# LV_Schematic.net
KiCad netlist of a schematic drawn in Altium Designer
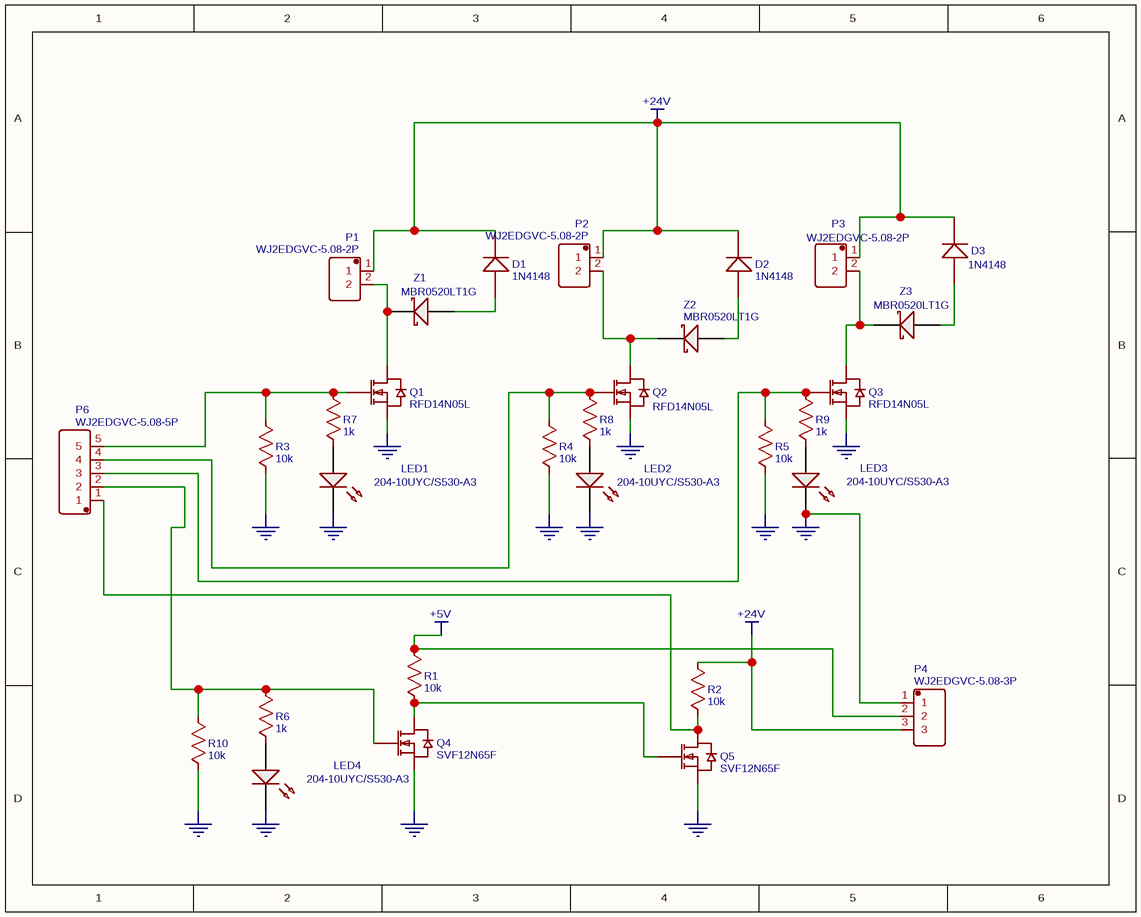
[diagram p0: LV+Schematic.schdoc]

(export (version "E")
  (design (tool "Eeschema 10.0.6"))
  (components
    (comp (ref "D1") (value "1N4148") (libsource (lib "") (part "root_1___1")))
    (comp (ref "D2") (value "1N4148") (libsource (lib "") (part "root_1___1")))
    (comp (ref "D3") (value "1N4148") (libsource (lib "") (part "root_1___1")))
    (comp (ref "LED1") (value "204-10UYC/S530-A3") (libsource (lib "altium-import") (part "root_3__")))
    (comp (ref "LED2") (value "204-10UYC/S530-A3") (libsource (lib "altium-import") (part "root_3__")))
    (comp (ref "LED3") (value "204-10UYC/S530-A3") (libsource (lib "altium-import") (part "root_3__")))
    (comp (ref "LED4") (value "204-10UYC/S530-A3") (libsource (lib "altium-import") (part "root_3__")))
    (comp (ref "P1")
      (value "WJ2EDGVC-5.08-2P")
      (fields (field (name "BOM_MANUFACTURER PART") "?"))
      (libsource (lib "") (part "root_0___3"))
    )
    (comp (ref "P2")
      (value "WJ2EDGVC-5.08-2P")
      (fields (field (name "BOM_MANUFACTURER PART") "?"))
      (libsource (lib "") (part "root_0___3"))
    )
    (comp (ref "P3")
      (value "WJ2EDGVC-5.08-2P")
      (fields (field (name "BOM_MANUFACTURER PART") "?"))
      (libsource (lib "") (part "root_0___3"))
    )
    (comp (ref "P4")
      (value "WJ2EDGVC-5.08-3P")
      (fields (field (name "BOM_MANUFACTURER PART") "?"))
      (libsource (lib "") (part "root_0___2"))
    )
    (comp (ref "P6")
      (value "WJ2EDGVC-5.08-5P")
      (fields (field (name "BOM_MANUFACTURER PART") "?"))
      (libsource (lib "altium-import") (part "root_2__"))
    )
    (comp (ref "Q1")
      (value "RFD14N05L")
      (fields (field (name "BOM_MANUFACTURER PART") "SVF12N65F"))
      (libsource (lib "altium-import") (part "root_0__"))
    )
    (comp (ref "Q2")
      (value "RFD14N05L")
      (fields (field (name "BOM_MANUFACTURER PART") "SVF12N65F"))
      (libsource (lib "altium-import") (part "root_0__"))
    )
    (comp (ref "Q3")
      (value "RFD14N05L")
      (fields (field (name "BOM_MANUFACTURER PART") "SVF12N65F"))
      (libsource (lib "altium-import") (part "root_0__"))
    )
    (comp (ref "Q4") (value "SVF12N65F") (libsource (lib "altium-import") (part "root_0__")))
    (comp (ref "Q5") (value "SVF12N65F") (libsource (lib "altium-import") (part "root_0__")))
    (comp (ref "R1")
      (value "10k")
      (fields (field (name "BOM_MANUFACTURER PART") "?"))
      (libsource (lib "altium-import") (part "root_1__"))
    )
    (comp (ref "R2")
      (value "10k")
      (fields (field (name "BOM_MANUFACTURER PART") "?"))
      (libsource (lib "altium-import") (part "root_1__"))
    )
    (comp (ref "R3")
      (value "10k")
      (fields (field (name "BOM_MANUFACTURER PART") "?"))
      (libsource (lib "altium-import") (part "root_1__"))
    )
    (comp (ref "R4")
      (value "10k")
      (fields (field (name "BOM_MANUFACTURER PART") "?"))
      (libsource (lib "altium-import") (part "root_1__"))
    )
    (comp (ref "R5")
      (value "10k")
      (fields (field (name "BOM_MANUFACTURER PART") "?"))
      (libsource (lib "altium-import") (part "root_1__"))
    )
    (comp (ref "R6")
      (value "1k")
      (fields (field (name "BOM_MANUFACTURER PART") "?"))
      (libsource (lib "altium-import") (part "root_1__"))
    )
    (comp (ref "R7")
      (value "1k")
      (fields (field (name "BOM_MANUFACTURER PART") "?"))
      (libsource (lib "altium-import") (part "root_1__"))
    )
    (comp (ref "R8")
      (value "1k")
      (fields (field (name "BOM_MANUFACTURER PART") "?"))
      (libsource (lib "altium-import") (part "root_1__"))
    )
    (comp (ref "R9")
      (value "1k")
      (fields (field (name "BOM_MANUFACTURER PART") "?"))
      (libsource (lib "altium-import") (part "root_1__"))
    )
    (comp (ref "R10")
      (value "10k")
      (fields (field (name "BOM_MANUFACTURER PART") "?"))
      (libsource (lib "altium-import") (part "root_1__"))
    )
    (comp (ref "Z1") (value "MBR0520LT1G") (libsource (lib "") (part "root_0___1")))
    (comp (ref "Z2") (value "MBR0520LT1G") (libsource (lib "") (part "root_0___1")))
    (comp (ref "Z3") (value "MBR0520LT1G") (libsource (lib "") (part "root_0___1")))
  )
  (nets
    (net (code "1") (name "+5V") (class "Default")
      (node (ref "P4") (pin "2") (pinfunction "2_2") (pintype "passive"))
      (node (ref "R1") (pin "2") (pinfunction "2_2") (pintype "passive"))
    )
    (net (code "2") (name "+24V") (class "Default")
      (node (ref "D1") (pin "2") (pinfunction "K_2") (pintype "passive"))
      (node (ref "D2") (pin "2") (pinfunction "K_2") (pintype "passive"))
      (node (ref "D3") (pin "2") (pinfunction "K_2") (pintype "passive"))
      (node (ref "P1") (pin "1") (pinfunction "1_1") (pintype "passive"))
      (node (ref "P2") (pin "1") (pinfunction "1_1") (pintype "passive"))
      (node (ref "P3") (pin "1") (pinfunction "1_1") (pintype "passive"))
      (node (ref "P4") (pin "3") (pinfunction "3_3") (pintype "passive"))
      (node (ref "R2") (pin "2") (pinfunction "2_2") (pintype "passive"))
    )
    (net (code "3") (name "GND") (class "Default")
      (node (ref "LED1") (pin "2") (pinfunction "C_2") (pintype "passive"))
      (node (ref "LED2") (pin "2") (pinfunction "C_2") (pintype "passive"))
      (node (ref "LED3") (pin "2") (pinfunction "C_2") (pintype "passive"))
      (node (ref "LED4") (pin "2") (pinfunction "C_2") (pintype "passive"))
      (node (ref "P4") (pin "1") (pinfunction "1_1") (pintype "passive"))
      (node (ref "Q1") (pin "3") (pinfunction "S_3") (pintype "passive"))
      (node (ref "Q2") (pin "3") (pinfunction "S_3") (pintype "passive"))
      (node (ref "Q3") (pin "3") (pinfunction "S_3") (pintype "passive"))
      (node (ref "Q4") (pin "3") (pinfunction "S_3") (pintype "passive"))
      (node (ref "Q5") (pin "3") (pinfunction "S_3") (pintype "passive"))
      (node (ref "R10") (pin "1") (pinfunction "1_1") (pintype "passive"))
      (node (ref "R3") (pin "1") (pinfunction "1_1") (pintype "passive"))
      (node (ref "R4") (pin "1") (pinfunction "1_1") (pintype "passive"))
      (node (ref "R5") (pin "1") (pinfunction "1_1") (pintype "passive"))
    )
    (net (code "4") (name "Net-(D1-A)") (class "Default")
      (node (ref "D1") (pin "1") (pinfunction "A_1") (pintype "passive"))
      (node (ref "Z1") (pin "1") (pinfunction "A_1") (pintype "passive"))
    )
    (net (code "5") (name "Net-(D2-A)") (class "Default")
      (node (ref "D2") (pin "1") (pinfunction "A_1") (pintype "passive"))
      (node (ref "Z2") (pin "1") (pinfunction "A_1") (pintype "passive"))
    )
    (net (code "6") (name "Net-(D3-A)") (class "Default")
      (node (ref "D3") (pin "1") (pinfunction "A_1") (pintype "passive"))
      (node (ref "Z3") (pin "1") (pinfunction "A_1") (pintype "passive"))
    )
    (net (code "7") (name "Net-(LED1-A)") (class "Default")
      (node (ref "LED1") (pin "1") (pinfunction "A_1") (pintype "passive"))
      (node (ref "R7") (pin "1") (pinfunction "1_1") (pintype "passive"))
    )
    (net (code "8") (name "Net-(LED2-A)") (class "Default")
      (node (ref "LED2") (pin "1") (pinfunction "A_1") (pintype "passive"))
      (node (ref "R8") (pin "1") (pinfunction "1_1") (pintype "passive"))
    )
    (net (code "9") (name "Net-(LED3-A)") (class "Default")
      (node (ref "LED3") (pin "1") (pinfunction "A_1") (pintype "passive"))
      (node (ref "R9") (pin "1") (pinfunction "1_1") (pintype "passive"))
    )
    (net (code "10") (name "Net-(LED4-A)") (class "Default")
      (node (ref "LED4") (pin "1") (pinfunction "A_1") (pintype "passive"))
      (node (ref "R6") (pin "1") (pinfunction "1_1") (pintype "passive"))
    )
    (net (code "11") (name "Net-(Q1-D)") (class "Default")
      (node (ref "P1") (pin "2") (pinfunction "2_2") (pintype "passive"))
      (node (ref "Q1") (pin "2") (pinfunction "D_2") (pintype "passive"))
      (node (ref "Z1") (pin "2") (pinfunction "K_2") (pintype "passive"))
    )
    (net (code "12") (name "Net-(Q1-G)") (class "Default")
      (node (ref "P6") (pin "5") (pinfunction "5_5") (pintype "passive"))
      (node (ref "Q1") (pin "1") (pinfunction "G_1") (pintype "passive"))
      (node (ref "R3") (pin "2") (pinfunction "2_2") (pintype "passive"))
      (node (ref "R7") (pin "2") (pinfunction "2_2") (pintype "passive"))
    )
    (net (code "13") (name "Net-(Q2-D)") (class "Default")
      (node (ref "P2") (pin "2") (pinfunction "2_2") (pintype "passive"))
      (node (ref "Q2") (pin "2") (pinfunction "D_2") (pintype "passive"))
      (node (ref "Z2") (pin "2") (pinfunction "K_2") (pintype "passive"))
    )
    (net (code "14") (name "Net-(Q2-G)") (class "Default")
      (node (ref "P6") (pin "4") (pinfunction "4_4") (pintype "passive"))
      (node (ref "Q2") (pin "1") (pinfunction "G_1") (pintype "passive"))
      (node (ref "R4") (pin "2") (pinfunction "2_2") (pintype "passive"))
      (node (ref "R8") (pin "2") (pinfunction "2_2") (pintype "passive"))
    )
    (net (code "15") (name "Net-(Q3-D)") (class "Default")
      (node (ref "P3") (pin "2") (pinfunction "2_2") (pintype "passive"))
      (node (ref "Q3") (pin "2") (pinfunction "D_2") (pintype "passive"))
      (node (ref "Z3") (pin "2") (pinfunction "K_2") (pintype "passive"))
    )
    (net (code "16") (name "Net-(Q3-G)") (class "Default")
      (node (ref "P6") (pin "3") (pinfunction "3_3") (pintype "passive"))
      (node (ref "Q3") (pin "1") (pinfunction "G_1") (pintype "passive"))
      (node (ref "R5") (pin "2") (pinfunction "2_2") (pintype "passive"))
      (node (ref "R9") (pin "2") (pinfunction "2_2") (pintype "passive"))
    )
    (net (code "17") (name "Net-(Q4-D)") (class "Default")
      (node (ref "Q4") (pin "2") (pinfunction "D_2") (pintype "passive"))
      (node (ref "Q5") (pin "1") (pinfunction "G_1") (pintype "passive"))
      (node (ref "R1") (pin "1") (pinfunction "1_1") (pintype "passive"))
    )
    (net (code "18") (name "Net-(Q4-G)") (class "Default")
      (node (ref "P6") (pin "2") (pinfunction "2_2") (pintype "passive"))
      (node (ref "Q4") (pin "1") (pinfunction "G_1") (pintype "passive"))
      (node (ref "R10") (pin "2") (pinfunction "2_2") (pintype "passive"))
      (node (ref "R6") (pin "2") (pinfunction "2_2") (pintype "passive"))
    )
    (net (code "19") (name "Net-(Q5-D)") (class "Default")
      (node (ref "P6") (pin "1") (pinfunction "1_1") (pintype "passive"))
      (node (ref "Q5") (pin "2") (pinfunction "D_2") (pintype "passive"))
      (node (ref "R2") (pin "1") (pinfunction "1_1") (pintype "passive"))
    )
  )
)
